# Rev_2.net
KiCad netlist of a schematic drawn in EAGLE
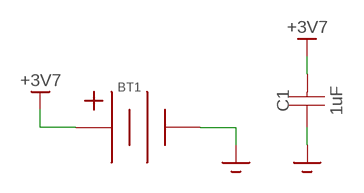
[diagram p0: schematic, sheet 1]
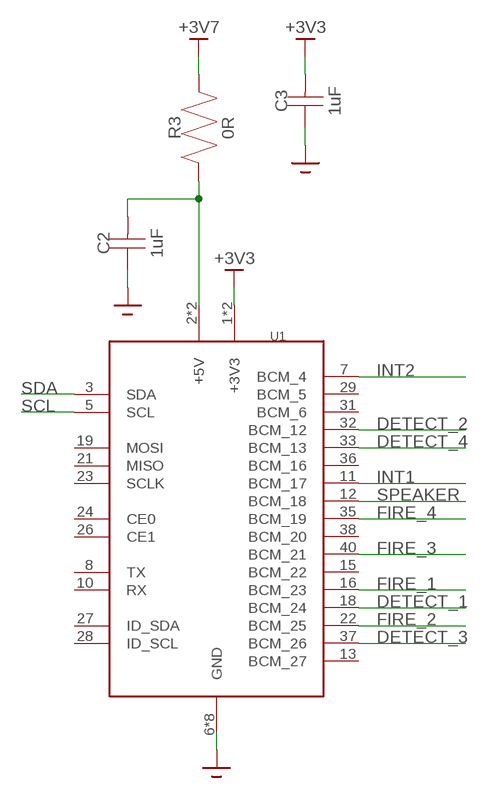
[diagram p1: schematic, sheet 2]
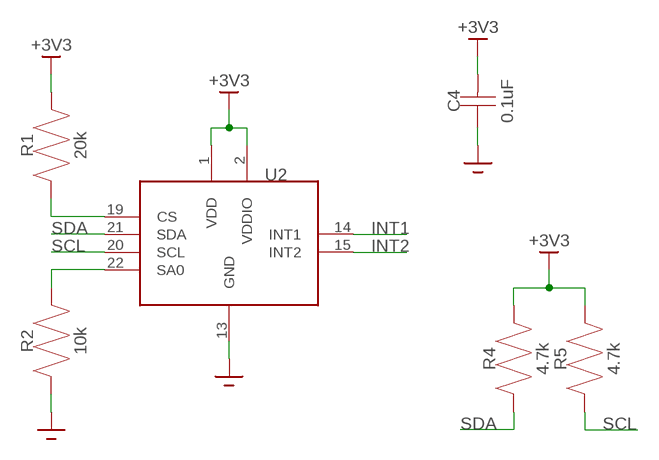
[diagram p2: schematic, sheet 3]
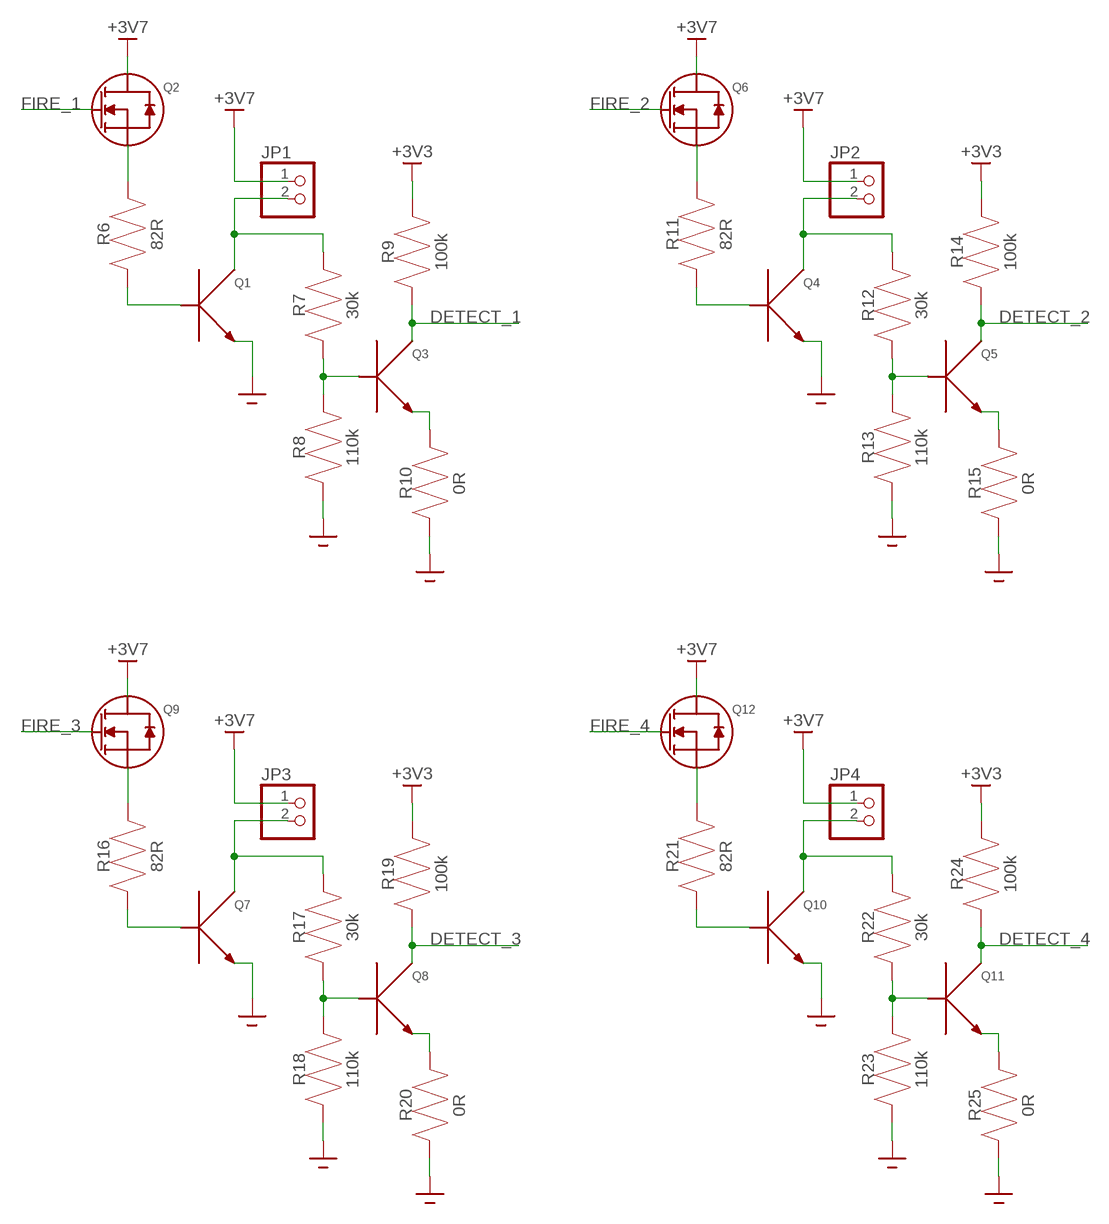
[diagram p3: schematic, sheet 4]
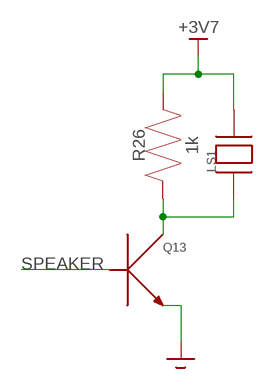
[diagram p4: schematic, sheet 5]

(export (version "E")
  (design (tool "Eeschema 10.0.6"))
  (components
    (comp (ref "C4")
      (value "0.1uF")
      (footprint "eagle-import:0805")
      (libsource (lib "eagle-import") (part "CAPACITOR0805"))
    )
    (comp (ref "R1")
      (value "20k")
      (footprint "eagle-import:0805")
      (libsource (lib "eagle-import") (part "RESISTOR0805"))
    )
    (comp (ref "R2")
      (value "10k")
      (footprint "eagle-import:0805")
      (libsource (lib "eagle-import") (part "RESISTOR0805"))
    )
    (comp (ref "R4")
      (value "4.7k")
      (footprint "eagle-import:0805")
      (libsource (lib "eagle-import") (part "RESISTOR0805"))
    )
    (comp (ref "R5")
      (value "4.7k")
      (footprint "eagle-import:0805")
      (libsource (lib "eagle-import") (part "RESISTOR0805"))
    )
    (comp (ref "U2")
      (value "STEVAL-MKIT01V1")
      (footprint "eagle-import:DIP1524W53P254L3302H1000Q24B")
      (libsource (lib "eagle-import") (part "STEVAL-MKIT01V1"))
    )
    (comp (ref "JP1")
      (value "PINHD-1X2")
      (footprint "eagle-import:1X02")
      (libsource (lib "eagle-import") (part "PINHD-1X2"))
    )
    (comp (ref "JP2")
      (value "PINHD-1X2")
      (footprint "eagle-import:1X02")
      (libsource (lib "eagle-import") (part "PINHD-1X2"))
    )
    (comp (ref "JP3")
      (value "PINHD-1X2")
      (footprint "eagle-import:1X02")
      (libsource (lib "eagle-import") (part "PINHD-1X2"))
    )
    (comp (ref "JP4")
      (value "PINHD-1X2")
      (footprint "eagle-import:1X02")
      (libsource (lib "eagle-import") (part "PINHD-1X2"))
    )
    (comp (ref "Q1")
      (value "3STF1640")
      (footprint "eagle-import:3STF1640")
      (libsource (lib "eagle-import") (part "3STF1640"))
    )
    (comp (ref "Q2")
      (value "DMN601K")
      (footprint "eagle-import:SOT91P240X110-3")
      (libsource (lib "eagle-import") (part "DMN601K"))
    )
    (comp (ref "Q3")
      (value "MMBT3904")
      (footprint "eagle-import:SOT96P237X112-3")
      (libsource (lib "eagle-import") (part "MMBT3904"))
    )
    (comp (ref "Q4")
      (value "3STF1640")
      (footprint "eagle-import:3STF1640")
      (libsource (lib "eagle-import") (part "3STF1640"))
    )
    (comp (ref "Q5")
      (value "MMBT3904")
      (footprint "eagle-import:SOT96P237X112-3")
      (libsource (lib "eagle-import") (part "MMBT3904"))
    )
    (comp (ref "Q6")
      (value "DMN601K")
      (footprint "eagle-import:SOT91P240X110-3")
      (libsource (lib "eagle-import") (part "DMN601K"))
    )
    (comp (ref "Q7")
      (value "3STF1640")
      (footprint "eagle-import:3STF1640")
      (libsource (lib "eagle-import") (part "3STF1640"))
    )
    (comp (ref "Q8")
      (value "MMBT3904")
      (footprint "eagle-import:SOT96P237X112-3")
      (libsource (lib "eagle-import") (part "MMBT3904"))
    )
    (comp (ref "Q9")
      (value "DMN601K")
      (footprint "eagle-import:SOT91P240X110-3")
      (libsource (lib "eagle-import") (part "DMN601K"))
    )
    (comp (ref "Q10")
      (value "3STF1640")
      (footprint "eagle-import:3STF1640")
      (libsource (lib "eagle-import") (part "3STF1640"))
    )
    (comp (ref "Q11")
      (value "MMBT3904")
      (footprint "eagle-import:SOT96P237X112-3")
      (libsource (lib "eagle-import") (part "MMBT3904"))
    )
    (comp (ref "Q12")
      (value "DMN601K")
      (footprint "eagle-import:SOT91P240X110-3")
      (libsource (lib "eagle-import") (part "DMN601K"))
    )
    (comp (ref "R6")
      (value "82R")
      (footprint "eagle-import:0805")
      (libsource (lib "eagle-import") (part "RESISTOR0805"))
    )
    (comp (ref "R7")
      (value "30k")
      (footprint "eagle-import:0805")
      (libsource (lib "eagle-import") (part "RESISTOR0805"))
    )
    (comp (ref "R8")
      (value "110k")
      (footprint "eagle-import:0805")
      (libsource (lib "eagle-import") (part "RESISTOR0805"))
    )
    (comp (ref "R9")
      (value "100k")
      (footprint "eagle-import:0805")
      (libsource (lib "eagle-import") (part "RESISTOR0805"))
    )
    (comp (ref "R10")
      (value "0R")
      (footprint "eagle-import:0805")
      (libsource (lib "eagle-import") (part "RESISTOR0805"))
    )
    (comp (ref "R11")
      (value "82R")
      (footprint "eagle-import:0805")
      (libsource (lib "eagle-import") (part "RESISTOR0805"))
    )
    (comp (ref "R12")
      (value "30k")
      (footprint "eagle-import:0805")
      (libsource (lib "eagle-import") (part "RESISTOR0805"))
    )
    (comp (ref "R13")
      (value "110k")
      (footprint "eagle-import:0805")
      (libsource (lib "eagle-import") (part "RESISTOR0805"))
    )
    (comp (ref "R14")
      (value "100k")
      (footprint "eagle-import:0805")
      (libsource (lib "eagle-import") (part "RESISTOR0805"))
    )
    (comp (ref "R15")
      (value "0R")
      (footprint "eagle-import:0805")
      (libsource (lib "eagle-import") (part "RESISTOR0805"))
    )
    (comp (ref "R16")
      (value "82R")
      (footprint "eagle-import:0805")
      (libsource (lib "eagle-import") (part "RESISTOR0805"))
    )
    (comp (ref "R17")
      (value "30k")
      (footprint "eagle-import:0805")
      (libsource (lib "eagle-import") (part "RESISTOR0805"))
    )
    (comp (ref "R18")
      (value "110k")
      (footprint "eagle-import:0805")
      (libsource (lib "eagle-import") (part "RESISTOR0805"))
    )
    (comp (ref "R19")
      (value "100k")
      (footprint "eagle-import:0805")
      (libsource (lib "eagle-import") (part "RESISTOR0805"))
    )
    (comp (ref "R20")
      (value "0R")
      (footprint "eagle-import:0805")
      (libsource (lib "eagle-import") (part "RESISTOR0805"))
    )
    (comp (ref "R21")
      (value "82R")
      (footprint "eagle-import:0805")
      (libsource (lib "eagle-import") (part "RESISTOR0805"))
    )
    (comp (ref "R22")
      (value "30k")
      (footprint "eagle-import:0805")
      (libsource (lib "eagle-import") (part "RESISTOR0805"))
    )
    (comp (ref "R23")
      (value "110k")
      (footprint "eagle-import:0805")
      (libsource (lib "eagle-import") (part "RESISTOR0805"))
    )
    (comp (ref "R24")
      (value "100k")
      (footprint "eagle-import:0805")
      (libsource (lib "eagle-import") (part "RESISTOR0805"))
    )
    (comp (ref "R25")
      (value "0R")
      (footprint "eagle-import:0805")
      (libsource (lib "eagle-import") (part "RESISTOR0805"))
    )
    (comp (ref "BT1")
      (value "18650")
      (footprint "eagle-import:18650")
      (libsource (lib "eagle-import") (part "18650"))
    )
    (comp (ref "C1")
      (value "1uF")
      (footprint "eagle-import:0805")
      (libsource (lib "eagle-import") (part "CAPACITOR0805"))
    )
    (comp (ref "LS1")
      (value "PKM13EPYH4000-A0")
      (footprint "eagle-import:PKM13EPYH4000-A0")
      (libsource (lib "eagle-import") (part "PKM13EPYH4000-A0"))
    )
    (comp (ref "Q13")
      (value "MMBT3904")
      (footprint "eagle-import:SOT96P237X112-3")
      (libsource (lib "eagle-import") (part "MMBT3904"))
    )
    (comp (ref "R26")
      (value "1k")
      (footprint "eagle-import:0805")
      (libsource (lib "eagle-import") (part "RESISTOR0805"))
    )
    (comp (ref "C2")
      (value "1uF")
      (footprint "eagle-import:0805")
      (libsource (lib "eagle-import") (part "CAPACITOR0805"))
    )
    (comp (ref "C3")
      (value "1uF")
      (footprint "eagle-import:0805")
      (libsource (lib "eagle-import") (part "CAPACITOR0805"))
    )
    (comp (ref "R3")
      (value "0R")
      (footprint "eagle-import:0805")
      (libsource (lib "eagle-import") (part "RESISTOR0805"))
    )
    (comp (ref "U1")
      (value "RPI-ZERO")
      (footprint "eagle-import:RPI-ZERO")
      (libsource (lib "eagle-import") (part "RPI-ZERO"))
    )
  )
  (nets
    (net (code "1") (name "+3V3") (class "Default")
      (node (ref "C3") (pin "P$2") (pinfunction "P$2_P$2") (pintype "passive"))
      (node (ref "C4") (pin "P$2") (pinfunction "P$2_P$2") (pintype "passive"))
      (node (ref "R1") (pin "P$2") (pinfunction "P$2_P$2") (pintype "passive"))
      (node (ref "R14") (pin "P$2") (pinfunction "P$2_P$2") (pintype "passive"))
      (node (ref "R19") (pin "P$2") (pinfunction "P$2_P$2") (pintype "passive"))
      (node (ref "R24") (pin "P$2") (pinfunction "P$2_P$2") (pintype "passive"))
      (node (ref "R4") (pin "P$2") (pinfunction "P$2_P$2") (pintype "passive"))
      (node (ref "R5") (pin "P$2") (pinfunction "P$2_P$2") (pintype "passive"))
      (node (ref "R9") (pin "P$2") (pinfunction "P$2_P$2") (pintype "passive"))
      (node (ref "U1") (pin "1") (pinfunction "+3V3_1") (pintype "power_in"))
      (node (ref "U1") (pin "17") (pinfunction "+3V3_17") (pintype "power_in"))
      (node (ref "U2") (pin "1") (pinfunction "VDD_1") (pintype "power_in"))
      (node (ref "U2") (pin "2") (pinfunction "VDDIO_2") (pintype "power_in"))
    )
    (net (code "2") (name "+3V7") (class "Default")
      (node (ref "BT1") (pin "+1") (pinfunction "+_+1") (pintype "power_in"))
      (node (ref "BT1") (pin "+2") (pinfunction "+_+2") (pintype "power_in"))
      (node (ref "BT1") (pin "+3") (pinfunction "+_+3") (pintype "power_in"))
      (node (ref "C1") (pin "P$2") (pinfunction "P$2_P$2") (pintype "passive"))
      (node (ref "JP1") (pin "1") (pinfunction "1_1") (pintype "passive"))
      (node (ref "JP2") (pin "1") (pinfunction "1_1") (pintype "passive"))
      (node (ref "JP3") (pin "1") (pinfunction "1_1") (pintype "passive"))
      (node (ref "JP4") (pin "1") (pinfunction "1_1") (pintype "passive"))
      (node (ref "LS1") (pin "P2") (pinfunction "P$2_P2") (pintype "bidirectional"))
      (node (ref "Q12") (pin "3") (pinfunction "D_3") (pintype "bidirectional"))
      (node (ref "Q2") (pin "3") (pinfunction "D_3") (pintype "bidirectional"))
      (node (ref "Q6") (pin "3") (pinfunction "D_3") (pintype "bidirectional"))
      (node (ref "Q9") (pin "3") (pinfunction "D_3") (pintype "bidirectional"))
      (node (ref "R26") (pin "P$2") (pinfunction "P$2_P$2") (pintype "passive"))
      (node (ref "R3") (pin "P$2") (pinfunction "P$2_P$2") (pintype "passive"))
    )
    (net (code "3") (name "DETECT_1") (class "Default")
      (node (ref "Q3") (pin "3") (pinfunction "C_3") (pintype "bidirectional"))
      (node (ref "R9") (pin "P$1") (pinfunction "P$1_P$1") (pintype "passive"))
      (node (ref "U1") (pin "18") (pinfunction "BCM_24_18") (pintype "bidirectional"))
    )
    (net (code "4") (name "DETECT_2") (class "Default")
      (node (ref "Q5") (pin "3") (pinfunction "C_3") (pintype "bidirectional"))
      (node (ref "R14") (pin "P$1") (pinfunction "P$1_P$1") (pintype "passive"))
      (node (ref "U1") (pin "32") (pinfunction "BCM_12_32") (pintype "bidirectional"))
    )
    (net (code "5") (name "DETECT_3") (class "Default")
      (node (ref "Q8") (pin "3") (pinfunction "C_3") (pintype "bidirectional"))
      (node (ref "R19") (pin "P$1") (pinfunction "P$1_P$1") (pintype "passive"))
      (node (ref "U1") (pin "37") (pinfunction "BCM_26_37") (pintype "bidirectional"))
    )
    (net (code "6") (name "DETECT_4") (class "Default")
      (node (ref "Q11") (pin "3") (pinfunction "C_3") (pintype "bidirectional"))
      (node (ref "R24") (pin "P$1") (pinfunction "P$1_P$1") (pintype "passive"))
      (node (ref "U1") (pin "33") (pinfunction "BCM_13_33") (pintype "bidirectional"))
    )
    (net (code "7") (name "FIRE_1") (class "Default")
      (node (ref "Q2") (pin "1") (pinfunction "G_1") (pintype "bidirectional"))
      (node (ref "U1") (pin "16") (pinfunction "BCM_23_16") (pintype "bidirectional"))
    )
    (net (code "8") (name "FIRE_2") (class "Default")
      (node (ref "Q6") (pin "1") (pinfunction "G_1") (pintype "bidirectional"))
      (node (ref "U1") (pin "22") (pinfunction "BCM_25_22") (pintype "bidirectional"))
    )
    (net (code "9") (name "FIRE_3") (class "Default")
      (node (ref "Q9") (pin "1") (pinfunction "G_1") (pintype "bidirectional"))
      (node (ref "U1") (pin "40") (pinfunction "BCM_21_40") (pintype "bidirectional"))
    )
    (net (code "10") (name "FIRE_4") (class "Default")
      (node (ref "Q12") (pin "1") (pinfunction "G_1") (pintype "bidirectional"))
      (node (ref "U1") (pin "35") (pinfunction "BCM_19_35") (pintype "bidirectional"))
    )
    (net (code "11") (name "GND") (class "Default")
      (node (ref "BT1") (pin "-1") (pinfunction "-_-1") (pintype "passive"))
      (node (ref "BT1") (pin "-2") (pinfunction "-_-2") (pintype "passive"))
      (node (ref "BT1") (pin "-3") (pinfunction "-_-3") (pintype "passive"))
      (node (ref "C1") (pin "P$1") (pinfunction "P$1_P$1") (pintype "passive"))
      (node (ref "C2") (pin "P$1") (pinfunction "P$1_P$1") (pintype "passive"))
      (node (ref "C3") (pin "P$1") (pinfunction "P$1_P$1") (pintype "passive"))
      (node (ref "C4") (pin "P$1") (pinfunction "P$1_P$1") (pintype "passive"))
      (node (ref "Q1") (pin "P3") (pinfunction "E_P3") (pintype "bidirectional"))
      (node (ref "Q10") (pin "P3") (pinfunction "E_P3") (pintype "bidirectional"))
      (node (ref "Q13") (pin "2") (pinfunction "E_2") (pintype "bidirectional"))
      (node (ref "Q4") (pin "P3") (pinfunction "E_P3") (pintype "bidirectional"))
      (node (ref "Q7") (pin "P3") (pinfunction "E_P3") (pintype "bidirectional"))
      (node (ref "R10") (pin "P$1") (pinfunction "P$1_P$1") (pintype "passive"))
      (node (ref "R13") (pin "P$1") (pinfunction "P$1_P$1") (pintype "passive"))
      (node (ref "R15") (pin "P$1") (pinfunction "P$1_P$1") (pintype "passive"))
      (node (ref "R18") (pin "P$1") (pinfunction "P$1_P$1") (pintype "passive"))
      (node (ref "R2") (pin "P$1") (pinfunction "P$1_P$1") (pintype "passive"))
      (node (ref "R20") (pin "P$1") (pinfunction "P$1_P$1") (pintype "passive"))
      (node (ref "R23") (pin "P$1") (pinfunction "P$1_P$1") (pintype "passive"))
      (node (ref "R25") (pin "P$1") (pinfunction "P$1_P$1") (pintype "passive"))
      (node (ref "R8") (pin "P$1") (pinfunction "P$1_P$1") (pintype "passive"))
      (node (ref "U1") (pin "14") (pinfunction "GND_14") (pintype "passive"))
      (node (ref "U1") (pin "20") (pinfunction "GND_20") (pintype "passive"))
      (node (ref "U1") (pin "25") (pinfunction "GND_25") (pintype "passive"))
      (node (ref "U1") (pin "30") (pinfunction "GND_30") (pintype "passive"))
      (node (ref "U1") (pin "34") (pinfunction "GND_34") (pintype "passive"))
      (node (ref "U1") (pin "39") (pinfunction "GND_39") (pintype "passive"))
      (node (ref "U1") (pin "6") (pinfunction "GND_6") (pintype "passive"))
      (node (ref "U1") (pin "9") (pinfunction "GND_9") (pintype "passive"))
      (node (ref "U2") (pin "13") (pinfunction "GND_13") (pintype "passive"))
    )
    (net (code "12") (name "INT1") (class "Default")
      (node (ref "U1") (pin "11") (pinfunction "BCM_17_11") (pintype "bidirectional"))
      (node (ref "U2") (pin "14") (pinfunction "INT1_14") (pintype "bidirectional"))
    )
    (net (code "13") (name "INT2") (class "Default")
      (node (ref "U1") (pin "7") (pinfunction "BCM_4_7") (pintype "bidirectional"))
      (node (ref "U2") (pin "15") (pinfunction "INT2_15") (pintype "bidirectional"))
    )
    (net (code "14") (name "Net-(C2-PadP$2)") (class "Default")
      (node (ref "C2") (pin "P$2") (pinfunction "P$2_P$2") (pintype "passive"))
      (node (ref "R3") (pin "P$1") (pinfunction "P$1_P$1") (pintype "passive"))
      (node (ref "U1") (pin "2") (pinfunction "+5V_2") (pintype "power_in"))
      (node (ref "U1") (pin "4") (pinfunction "+5V_4") (pintype "power_in"))
    )
    (net (code "15") (name "Net-(JP1-Pad2)") (class "Default")
      (node (ref "JP1") (pin "2") (pinfunction "2_2") (pintype "passive"))
      (node (ref "Q1") (pin "P2") (pinfunction "C_P2") (pintype "bidirectional"))
      (node (ref "Q1") (pin "P4") (pinfunction "C_P4") (pintype "bidirectional"))
      (node (ref "Q1") (pin "P5") (pinfunction "C_P5") (pintype "bidirectional"))
      (node (ref "R7") (pin "P$2") (pinfunction "P$2_P$2") (pintype "passive"))
    )
    (net (code "16") (name "Net-(JP2-Pad2)") (class "Default")
      (node (ref "JP2") (pin "2") (pinfunction "2_2") (pintype "passive"))
      (node (ref "Q4") (pin "P2") (pinfunction "C_P2") (pintype "bidirectional"))
      (node (ref "Q4") (pin "P4") (pinfunction "C_P4") (pintype "bidirectional"))
      (node (ref "Q4") (pin "P5") (pinfunction "C_P5") (pintype "bidirectional"))
      (node (ref "R12") (pin "P$2") (pinfunction "P$2_P$2") (pintype "passive"))
    )
    (net (code "17") (name "Net-(JP3-Pad2)") (class "Default")
      (node (ref "JP3") (pin "2") (pinfunction "2_2") (pintype "passive"))
      (node (ref "Q7") (pin "P2") (pinfunction "C_P2") (pintype "bidirectional"))
      (node (ref "Q7") (pin "P4") (pinfunction "C_P4") (pintype "bidirectional"))
      (node (ref "Q7") (pin "P5") (pinfunction "C_P5") (pintype "bidirectional"))
      (node (ref "R17") (pin "P$2") (pinfunction "P$2_P$2") (pintype "passive"))
    )
    (net (code "18") (name "Net-(JP4-Pad2)") (class "Default")
      (node (ref "JP4") (pin "2") (pinfunction "2_2") (pintype "passive"))
      (node (ref "Q10") (pin "P2") (pinfunction "C_P2") (pintype "bidirectional"))
      (node (ref "Q10") (pin "P4") (pinfunction "C_P4") (pintype "bidirectional"))
      (node (ref "Q10") (pin "P5") (pinfunction "C_P5") (pintype "bidirectional"))
      (node (ref "R22") (pin "P$2") (pinfunction "P$2_P$2") (pintype "passive"))
    )
    (net (code "19") (name "Net-(LS1-P$1)") (class "Default")
      (node (ref "LS1") (pin "P1") (pinfunction "P$1_P1") (pintype "bidirectional"))
      (node (ref "Q13") (pin "3") (pinfunction "C_3") (pintype "bidirectional"))
      (node (ref "R26") (pin "P$1") (pinfunction "P$1_P$1") (pintype "passive"))
    )
    (net (code "20") (name "Net-(Q1-B)") (class "Default")
      (node (ref "Q1") (pin "P1") (pinfunction "B_P1") (pintype "bidirectional"))
      (node (ref "R6") (pin "P$1") (pinfunction "P$1_P$1") (pintype "passive"))
    )
    (net (code "21") (name "Net-(Q2-S)") (class "Default")
      (node (ref "Q2") (pin "2") (pinfunction "S_2") (pintype "bidirectional"))
      (node (ref "R6") (pin "P$2") (pinfunction "P$2_P$2") (pintype "passive"))
    )
    (net (code "22") (name "Net-(Q3-B)") (class "Default")
      (node (ref "Q3") (pin "1") (pinfunction "B_1") (pintype "bidirectional"))
      (node (ref "R7") (pin "P$1") (pinfunction "P$1_P$1") (pintype "passive"))
      (node (ref "R8") (pin "P$2") (pinfunction "P$2_P$2") (pintype "passive"))
    )
    (net (code "23") (name "Net-(Q3-E)") (class "Default")
      (node (ref "Q3") (pin "2") (pinfunction "E_2") (pintype "bidirectional"))
      (node (ref "R10") (pin "P$2") (pinfunction "P$2_P$2") (pintype "passive"))
    )
    (net (code "24") (name "Net-(Q4-B)") (class "Default")
      (node (ref "Q4") (pin "P1") (pinfunction "B_P1") (pintype "bidirectional"))
      (node (ref "R11") (pin "P$1") (pinfunction "P$1_P$1") (pintype "passive"))
    )
    (net (code "25") (name "Net-(Q5-B)") (class "Default")
      (node (ref "Q5") (pin "1") (pinfunction "B_1") (pintype "bidirectional"))
      (node (ref "R12") (pin "P$1") (pinfunction "P$1_P$1") (pintype "passive"))
      (node (ref "R13") (pin "P$2") (pinfunction "P$2_P$2") (pintype "passive"))
    )
    (net (code "26") (name "Net-(Q5-E)") (class "Default")
      (node (ref "Q5") (pin "2") (pinfunction "E_2") (pintype "bidirectional"))
      (node (ref "R15") (pin "P$2") (pinfunction "P$2_P$2") (pintype "passive"))
    )
    (net (code "27") (name "Net-(Q6-S)") (class "Default")
      (node (ref "Q6") (pin "2") (pinfunction "S_2") (pintype "bidirectional"))
      (node (ref "R11") (pin "P$2") (pinfunction "P$2_P$2") (pintype "passive"))
    )
    (net (code "28") (name "Net-(Q7-B)") (class "Default")
      (node (ref "Q7") (pin "P1") (pinfunction "B_P1") (pintype "bidirectional"))
      (node (ref "R16") (pin "P$1") (pinfunction "P$1_P$1") (pintype "passive"))
    )
    (net (code "29") (name "Net-(Q8-B)") (class "Default")
      (node (ref "Q8") (pin "1") (pinfunction "B_1") (pintype "bidirectional"))
      (node (ref "R17") (pin "P$1") (pinfunction "P$1_P$1") (pintype "passive"))
      (node (ref "R18") (pin "P$2") (pinfunction "P$2_P$2") (pintype "passive"))
    )
    (net (code "30") (name "Net-(Q8-E)") (class "Default")
      (node (ref "Q8") (pin "2") (pinfunction "E_2") (pintype "bidirectional"))
      (node (ref "R20") (pin "P$2") (pinfunction "P$2_P$2") (pintype "passive"))
    )
    (net (code "31") (name "Net-(Q9-S)") (class "Default")
      (node (ref "Q9") (pin "2") (pinfunction "S_2") (pintype "bidirectional"))
      (node (ref "R16") (pin "P$2") (pinfunction "P$2_P$2") (pintype "passive"))
    )
    (net (code "32") (name "Net-(Q10-B)") (class "Default")
      (node (ref "Q10") (pin "P1") (pinfunction "B_P1") (pintype "bidirectional"))
      (node (ref "R21") (pin "P$1") (pinfunction "P$1_P$1") (pintype "passive"))
    )
    (net (code "33") (name "Net-(Q11-B)") (class "Default")
      (node (ref "Q11") (pin "1") (pinfunction "B_1") (pintype "bidirectional"))
      (node (ref "R22") (pin "P$1") (pinfunction "P$1_P$1") (pintype "passive"))
      (node (ref "R23") (pin "P$2") (pinfunction "P$2_P$2") (pintype "passive"))
    )
    (net (code "34") (name "Net-(Q11-E)") (class "Default")
      (node (ref "Q11") (pin "2") (pinfunction "E_2") (pintype "bidirectional"))
      (node (ref "R25") (pin "P$2") (pinfunction "P$2_P$2") (pintype "passive"))
    )
    (net (code "35") (name "Net-(Q12-S)") (class "Default")
      (node (ref "Q12") (pin "2") (pinfunction "S_2") (pintype "bidirectional"))
      (node (ref "R21") (pin "P$2") (pinfunction "P$2_P$2") (pintype "passive"))
    )
    (net (code "36") (name "Net-(U2-CS)") (class "Default")
      (node (ref "R1") (pin "P$1") (pinfunction "P$1_P$1") (pintype "passive"))
      (node (ref "U2") (pin "19") (pinfunction "CS_19") (pintype "bidirectional"))
    )
    (net (code "37") (name "Net-(U2-SA0)") (class "Default")
      (node (ref "R2") (pin "P$2") (pinfunction "P$2_P$2") (pintype "passive"))
      (node (ref "U2") (pin "22") (pinfunction "SA0_22") (pintype "bidirectional"))
    )
    (net (code "38") (name "SCL") (class "Default")
      (node (ref "R5") (pin "P$1") (pinfunction "P$1_P$1") (pintype "passive"))
      (node (ref "U1") (pin "5") (pinfunction "SCL_5") (pintype "bidirectional"))
      (node (ref "U2") (pin "20") (pinfunction "SCL_20") (pintype "bidirectional"))
    )
    (net (code "39") (name "SDA") (class "Default")
      (node (ref "R4") (pin "P$1") (pinfunction "P$1_P$1") (pintype "passive"))
      (node (ref "U1") (pin "3") (pinfunction "SDA_3") (pintype "bidirectional"))
      (node (ref "U2") (pin "21") (pinfunction "SDA_21") (pintype "bidirectional"))
    )
    (net (code "40") (name "SPEAKER") (class "Default")
      (node (ref "Q13") (pin "1") (pinfunction "B_1") (pintype "bidirectional"))
      (node (ref "U1") (pin "12") (pinfunction "BCM_18_12") (pintype "bidirectional"))
    )
    (net (code "41") (name "unconnected-(U1-BCM_5-Pad29)") (class "Default")
      (node (ref "U1") (pin "29") (pinfunction "BCM_5_29") (pintype "bidirectional"))
    )
    (net (code "42") (name "unconnected-(U1-BCM_6-Pad31)") (class "Default")
      (node (ref "U1") (pin "31") (pinfunction "BCM_6_31") (pintype "bidirectional"))
    )
    (net (code "43") (name "unconnected-(U1-BCM_16-Pad36)") (class "Default")
      (node (ref "U1") (pin "36") (pinfunction "BCM_16_36") (pintype "bidirectional"))
    )
    (net (code "44") (name "unconnected-(U1-BCM_20-Pad38)") (class "Default")
      (node (ref "U1") (pin "38") (pinfunction "BCM_20_38") (pintype "bidirectional"))
    )
    (net (code "45") (name "unconnected-(U1-BCM_22-Pad15)") (class "Default")
      (node (ref "U1") (pin "15") (pinfunction "BCM_22_15") (pintype "bidirectional"))
    )
    (net (code "46") (name "unconnected-(U1-BCM_27-Pad13)") (class "Default")
      (node (ref "U1") (pin "13") (pinfunction "BCM_27_13") (pintype "bidirectional"))
    )
    (net (code "47") (name "unconnected-(U1-CE0-Pad24)") (class "Default")
      (node (ref "U1") (pin "24") (pinfunction "CE0_24") (pintype "bidirectional"))
    )
    (net (code "48") (name "unconnected-(U1-CE1-Pad26)") (class "Default")
      (node (ref "U1") (pin "26") (pinfunction "CE1_26") (pintype "bidirectional"))
    )
    (net (code "49") (name "unconnected-(U1-ID_SCL-Pad28)") (class "Default")
      (node (ref "U1") (pin "28") (pinfunction "ID_SCL_28") (pintype "bidirectional"))
    )
    (net (code "50") (name "unconnected-(U1-ID_SDA-Pad27)") (class "Default")
      (node (ref "U1") (pin "27") (pinfunction "ID_SDA_27") (pintype "bidirectional"))
    )
    (net (code "51") (name "unconnected-(U1-MISO-Pad21)") (class "Default")
      (node (ref "U1") (pin "21") (pinfunction "MISO_21") (pintype "bidirectional"))
    )
    (net (code "52") (name "unconnected-(U1-MOSI-Pad19)") (class "Default")
      (node (ref "U1") (pin "19") (pinfunction "MOSI_19") (pintype "bidirectional"))
    )
    (net (code "53") (name "unconnected-(U1-RX-Pad10)") (class "Default")
      (node (ref "U1") (pin "10") (pinfunction "RX_10") (pintype "bidirectional"))
    )
    (net (code "54") (name "unconnected-(U1-SCLK-Pad23)") (class "Default")
      (node (ref "U1") (pin "23") (pinfunction "SCLK_23") (pintype "bidirectional"))
    )
    (net (code "55") (name "unconnected-(U1-TX-Pad8)") (class "Default")
      (node (ref "U1") (pin "8") (pinfunction "TX_8") (pintype "bidirectional"))
    )
  )
)
